# BDSHOT_TX.net
KiCad netlist of a schematic drawn in Altium Designer
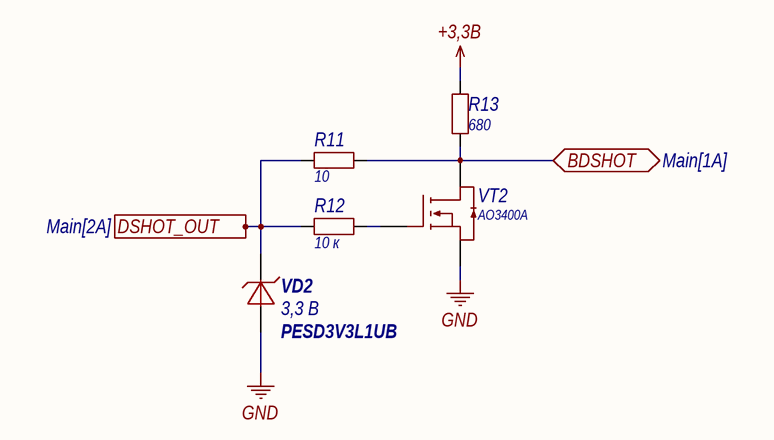
[diagram p0: BDSHOT_TX.SchDoc]

(export (version "E")
  (design (tool "Eeschema 10.0.6"))
  (components
    (comp (ref "R11")
      (value "10")
      (footprint "0603R")
      (description "Резистор номиналом 10 Ом и точностью 1%")
      (fields (field (name "PART NUMBER") "Resistor_10_1_0603") (field (name "TOLERANCE") "1%"))
      (libsource (lib "Hydrolib") (part "Resistor"))
    )
    (comp (ref "R12")
      (value "10 к")
      (footprint "0603R")
      (description "Резистор номиналом 10 кОм и точностью 1%")
      (fields (field (name "PART NUMBER") "Resistor_10k_1_0603") (field (name "TOLERANCE") "1%"))
      (libsource (lib "Hydrolib") (part "Resistor"))
    )
    (comp (ref "R13")
      (value "680")
      (footprint "0603R")
      (description "Резистор номиналом 680 Ом и точностью 1%")
      (fields (field (name "PART NUMBER") "Resistor_680_1_0603") (field (name "TOLERANCE") "1%"))
      (libsource (lib "") (part "Resistor_1"))
    )
    (comp (ref "VD2")
      (value "PESD3V3L1UB")
      (footprint "SOD523")
      (description "Защитный диод на 3,3 В, рассеиваемая мощность 45 Вт")
      (fields (field (name "ALTIUM_VALUE") "3,3 В"))
      (libsource (lib "Hydrolib") (part "TVS_1_1dir"))
    )
    (comp (ref "VT2")
      (value "AO3400A")
      (footprint "SOT23-3")
      (description "N-канальный MOSFET")
      (libsource (lib "Hydrolib") (part "MOSFET N-channel 2"))
    )
  )
  (nets
    (net (code "1") (name "+3,3В") (class "Default")
      (node (ref "R13") (pin "2") (pinfunction "2_2") (pintype "passive"))
    )
    (net (code "2") (name "/BDSHOT") (class "Default")
      (node (ref "R11") (pin "2") (pinfunction "2_2") (pintype "passive"))
      (node (ref "R13") (pin "1") (pinfunction "1_1") (pintype "passive"))
      (node (ref "VT2") (pin "3") (pinfunction "3_3") (pintype "passive"))
    )
    (net (code "3") (name "/DSHOT_OUT") (class "Default")
      (node (ref "R11") (pin "1") (pinfunction "1_1") (pintype "passive"))
      (node (ref "R12") (pin "1") (pinfunction "1_1") (pintype "passive"))
      (node (ref "VD2") (pin "2") (pinfunction "2_2") (pintype "passive"))
    )
    (net (code "4") (name "GND") (class "Default")
      (node (ref "VD2") (pin "1") (pinfunction "1_1") (pintype "passive"))
      (node (ref "VT2") (pin "2") (pinfunction "2_2") (pintype "passive"))
    )
    (net (code "5") (name "Net-(R12-Pad2)") (class "Default")
      (node (ref "R12") (pin "2") (pinfunction "2_2") (pintype "passive"))
      (node (ref "VT2") (pin "1") (pinfunction "1_1") (pintype "passive"))
    )
  )
)
